# PWR_P6V0.net
KiCad netlist of a schematic drawn in Altium Designer
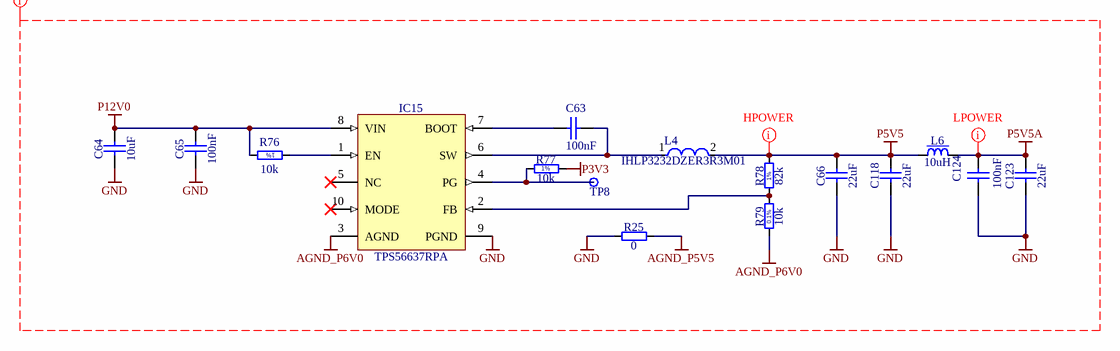
[diagram p0: PWR_P6V0.SchDoc]

(export (version "E")
  (design (tool "Eeschema 10.0.6"))
  (components
    (comp (ref "C63")
      (value "100nF")
      (footprint "CAPC1005X55N")
      (description "Non-polarised capacitor")
      (fields
        (field (name "PART NUMBER") "CC0402_100NF_16V_10%_X5R")
        (field (name "VOLTAGE") "16V")
        (field (name "AUTHOR") "CERN DEM JLC")
      )
      (libsource (lib "Capacitors") (part "Capacitor - non polarized"))
    )
    (comp (ref "C64")
      (value "10uF")
      (footprint "CAPC2012X95N")
      (description "Non-polarised capacitor")
      (fields
        (field (name "PART NUMBER") "CC0805_10UF_25V_10%_X5R")
        (field (name "VOLTAGE") "25V")
        (field (name "AUTHOR") "CERN DEM JLC")
      )
      (libsource (lib "Capacitors") (part "Capacitor - non polarized"))
    )
    (comp (ref "C65")
      (value "100nF")
      (footprint "CAPC1005X55N")
      (description "Non-polarised capacitor")
      (fields
        (field (name "PART NUMBER") "CC0402_100NF_16V_10%_X5R")
        (field (name "VOLTAGE") "16V")
        (field (name "AUTHOR") "CERN DEM JLC")
      )
      (libsource (lib "Capacitors") (part "Capacitor - non polarized"))
    )
    (comp (ref "C66")
      (value "22uF")
      (footprint "CAPC2012X135N")
      (description "Non-polarised capacitor")
      (fields
        (field (name "PART NUMBER") "CC0805_22UF_16V_10%_X5R")
        (field (name "VOLTAGE") "16V")
        (field (name "AUTHOR") "CERN DEM JLC")
      )
      (libsource (lib "Capacitors") (part "Capacitor - non polarized"))
    )
    (comp (ref "C118")
      (value "22uF")
      (footprint "CAPC2012X135N")
      (description "Non-polarised capacitor")
      (fields
        (field (name "PART NUMBER") "CC0805_22UF_16V_10%_X5R")
        (field (name "VOLTAGE") "16V")
        (field (name "AUTHOR") "CERN DEM JLC")
      )
      (libsource (lib "Capacitors") (part "Capacitor - non polarized"))
    )
    (comp (ref "C123")
      (value "22uF")
      (footprint "CAPC2012X135N")
      (description "Non-polarised capacitor")
      (fields
        (field (name "PART NUMBER") "CC0805_22UF_16V_10%_X5R")
        (field (name "VOLTAGE") "16V")
        (field (name "AUTHOR") "CERN DEM JLC")
      )
      (libsource (lib "Capacitors") (part "Capacitor - non polarized"))
    )
    (comp (ref "C124")
      (value "100nF")
      (footprint "CAPC1005X55N")
      (description "Non-polarised capacitor")
      (fields
        (field (name "PART NUMBER") "CC0402_100NF_16V_10%_X5R")
        (field (name "VOLTAGE") "16V")
        (field (name "AUTHOR") "CERN DEM JLC")
      )
      (libsource (lib "Capacitors") (part "Capacitor - non polarized"))
    )
    (comp (ref "IC15")
      (value "TPS56637RPA")
      (footprint "TEXAS_RPA0010A")
      (description "4.5V to 28V Input, 6A Synchronous Buck Converter")
      (fields (field (name "MANUFACTURER") "TEXAS INSTRUMENTS") (field (name "AUTHOR") "CERN DEM BC"))
      (libsource (lib "ICs And Semiconductors") (part "TPS56637RPA"))
    )
    (comp (ref "L4")
      (value "IHLP3232DZER3R3M01")
      (footprint "FP-IHLP-3232DZ-FP_2_413x5-MFG")
      (description "Commercial Inductors, Low DCR Series 3.3uH 9.2 A 17.7mΩ 20%")
      (fields (field (name "TOLERANCE") "20%"))
      (libsource (lib "Altium Content Vault") (part "725321dda6339637d4d059423bc1c3c"))
    )
    (comp (ref "L6")
      (value "10uH")
      (footprint "IND_MURATA-PS_8400")
      (description "Inductor With Core")
      (fields
        (field (name "PART NUMBER") "IND_10UH_10%_MURATA-PS_8400")
        (field (name "POWER") "950mA")
        (field (name "AUTHOR") "CERN DEM JLC")
      )
      (libsource (lib "Inductors & Transformers") (part "Inductor With Magnetic core"))
    )
    (comp (ref "R25")
      (value "0")
      (footprint "RESC1005X40N")
      (description "Resistor")
      (fields
        (field (name "PART NUMBER") "R0402_0R_JUMPER")
        (field (name "MANUFACTURER") "GENERIC")
        (field (name "AUTHOR") "CERN DEM JLC")
      )
      (libsource (lib "Resistors") (part "Resistor"))
    )
    (comp (ref "R76")
      (value "10k")
      (footprint "RESC1005X40N")
      (description "Resistor - 1%")
      (fields
        (field (name "PART NUMBER") "R0402_10K_1%_0.0625W_100PPM")
        (field (name "MANUFACTURER") "GENERIC")
        (field (name "AUTHOR") "CERN DEM JLC")
      )
      (libsource (lib "Resistors") (part "Resistor - 1%"))
    )
    (comp (ref "R77")
      (value "10k")
      (footprint "RESC1005X40N")
      (description "Resistor - 1%")
      (fields
        (field (name "PART NUMBER") "R0402_10K_1%_0.0625W_100PPM")
        (field (name "MANUFACTURER") "GENERIC")
        (field (name "AUTHOR") "CERN DEM JLC")
      )
      (libsource (lib "Resistors") (part "Resistor - 1%"))
    )
    (comp (ref "R78")
      (value "82k")
      (footprint "RESC1608X55N")
      (description "Resistor - 1%")
      (fields
        (field (name "PART NUMBER") "R0603_82K_1%_0.1W_100PPM")
        (field (name "MANUFACTURER") "GENERIC")
        (field (name "AUTHOR") "CERN DEM JLC")
      )
      (libsource (lib "Resistors") (part "Resistor - 1%"))
    )
    (comp (ref "R79")
      (value "10k")
      (footprint "RESC1608X55N")
      (description "Resistor - 0.1%")
      (fields
        (field (name "PART NUMBER") "R0603_10K_0.1%_0.063W_10PPM")
        (field (name "MANUFACTURER") "GENERIC")
        (field (name "AUTHOR") "CERN DEM JLC")
      )
      (libsource (lib "Resistors") (part "Resistor - 0.1%"))
    )
    (comp (ref "TP8")
      (value "Test Point")
      (footprint "TPS127")
      (fields (field (name "PART NUMBER") "SMD_PAD_1.27X1.27MM") (field (name "AUTHOR") "CERN DEM JLC"))
      (libsource (lib "Eletro-mechanical") (part "Test Point"))
    )
  )
  (nets
    (net (code "1") (name "AGND_P5V5") (class "Default")
      (node (ref "R25") (pin "2") (pinfunction "2_2") (pintype "passive"))
    )
    (net (code "2") (name "AGND_P6V0") (class "Default")
      (node (ref "IC15") (pin "3") (pinfunction "AGND_3") (pintype "power_in"))
      (node (ref "R79") (pin "1") (pinfunction "1_1") (pintype "passive"))
    )
    (net (code "3") (name "GND") (class "Default")
      (node (ref "C118") (pin "1") (pinfunction "1_1") (pintype "passive"))
      (node (ref "C123") (pin "1") (pinfunction "1_1") (pintype "passive"))
      (node (ref "C124") (pin "1") (pinfunction "1_1") (pintype "passive"))
      (node (ref "C64") (pin "1") (pinfunction "1_1") (pintype "passive"))
      (node (ref "C65") (pin "1") (pinfunction "1_1") (pintype "passive"))
      (node (ref "C66") (pin "1") (pinfunction "1_1") (pintype "passive"))
      (node (ref "IC15") (pin "9") (pinfunction "PGND_9") (pintype "power_in"))
      (node (ref "R25") (pin "1") (pinfunction "1_1") (pintype "passive"))
    )
    (net (code "4") (name "Net-(IC15-BOOT)") (class "Default")
      (node (ref "C63") (pin "2") (pinfunction "2_2") (pintype "passive"))
      (node (ref "IC15") (pin "7") (pinfunction "BOOT_7") (pintype "input"))
    )
    (net (code "5") (name "Net-(IC15-EN)") (class "Default")
      (node (ref "IC15") (pin "1") (pinfunction "EN_1") (pintype "input"))
      (node (ref "R76") (pin "1") (pinfunction "1_1") (pintype "passive"))
    )
    (net (code "6") (name "Net-(IC15-FB)") (class "Default")
      (node (ref "IC15") (pin "2") (pinfunction "FB_2") (pintype "input"))
      (node (ref "R78") (pin "1") (pinfunction "1_1") (pintype "passive"))
      (node (ref "R79") (pin "2") (pinfunction "2_2") (pintype "passive"))
    )
    (net (code "7") (name "Net-(IC15-PG)") (class "Default")
      (node (ref "IC15") (pin "4") (pinfunction "PG_4") (pintype "output"))
      (node (ref "R77") (pin "1") (pinfunction "1_1") (pintype "passive"))
      (node (ref "TP8") (pin "1") (pinfunction "1_1") (pintype "bidirectional"))
    )
    (net (code "8") (name "Net-(IC15-SW)") (class "Default")
      (node (ref "C63") (pin "1") (pinfunction "1_1") (pintype "passive"))
      (node (ref "IC15") (pin "6") (pinfunction "SW_6") (pintype "output"))
      (node (ref "L4") (pin "1") (pinfunction "1_1") (pintype "passive"))
    )
    (net (code "9") (name "P3V3") (class "Default")
      (node (ref "R77") (pin "2") (pinfunction "2_2") (pintype "passive"))
    )
    (net (code "10") (name "P5V5") (class "Default")
      (node (ref "C118") (pin "2") (pinfunction "2_2") (pintype "passive"))
      (node (ref "C66") (pin "2") (pinfunction "2_2") (pintype "passive"))
      (node (ref "L4") (pin "2") (pinfunction "2_2") (pintype "passive"))
      (node (ref "L6") (pin "1") (pinfunction "1_1") (pintype "passive"))
      (node (ref "R78") (pin "2") (pinfunction "2_2") (pintype "passive"))
    )
    (net (code "11") (name "P5V5A") (class "Default")
      (node (ref "C123") (pin "2") (pinfunction "2_2") (pintype "passive"))
      (node (ref "C124") (pin "2") (pinfunction "2_2") (pintype "passive"))
      (node (ref "L6") (pin "2") (pinfunction "2_2") (pintype "passive"))
    )
    (net (code "12") (name "P12V0") (class "Default")
      (node (ref "C64") (pin "2") (pinfunction "2_2") (pintype "passive"))
      (node (ref "C65") (pin "2") (pinfunction "2_2") (pintype "passive"))
      (node (ref "IC15") (pin "8") (pinfunction "VIN_8") (pintype "input"))
      (node (ref "R76") (pin "2") (pinfunction "2_2") (pintype "passive"))
    )
    (net (code "13") (name "unconnected-(IC15-MODE-Pad10)") (class "Default")
      (node (ref "IC15") (pin "10") (pinfunction "MODE_10") (pintype "input+no_connect"))
    )
    (net (code "14") (name "unconnected-(IC15-NC-Pad5)") (class "Default")
      (node (ref "IC15") (pin "5") (pinfunction "NC_5") (pintype "passive+no_connect"))
    )
  )
)
